# LiPower-Shield.net
KiCad netlist of a schematic drawn in EAGLE
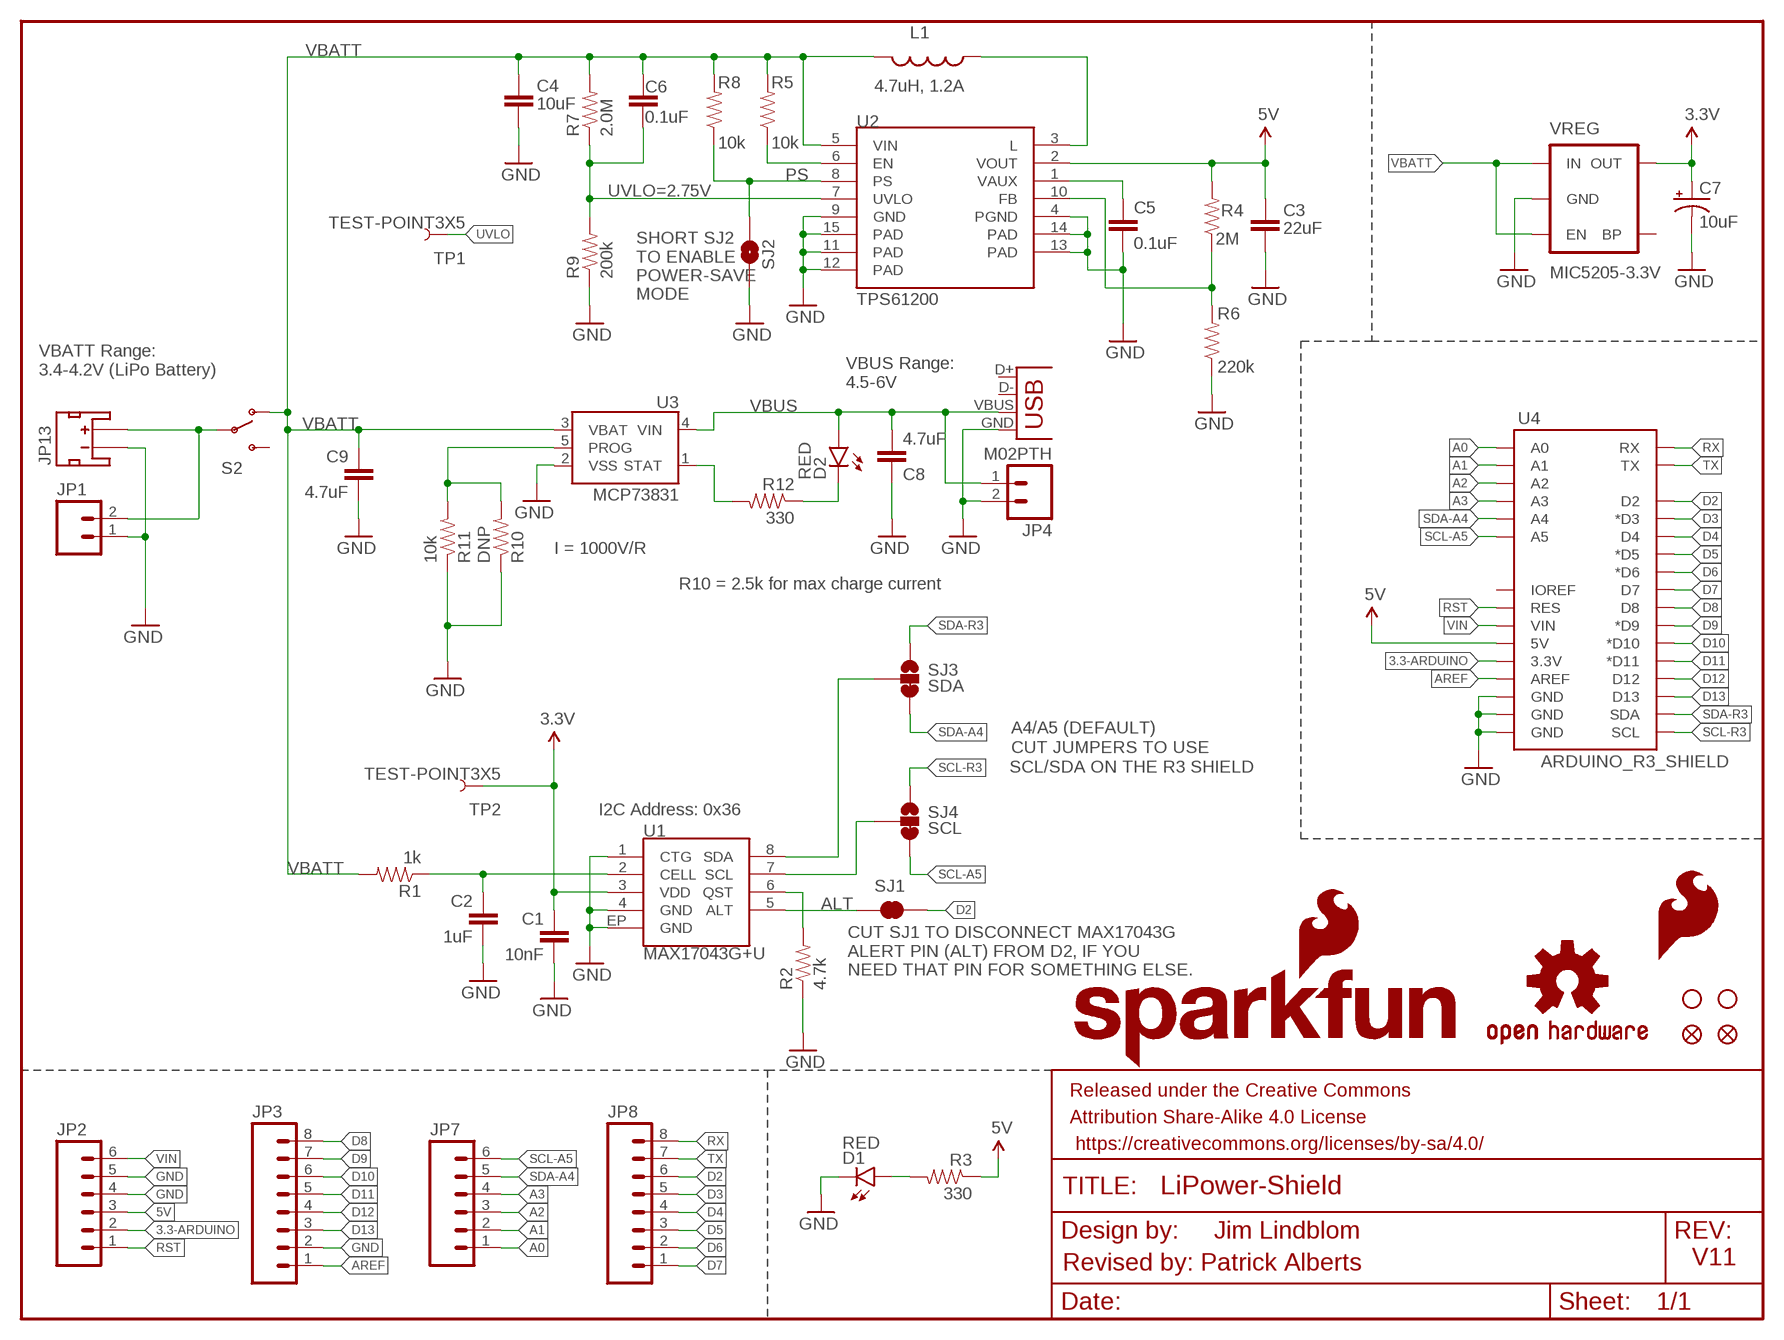
[diagram p0: schematic, sheet 1]

(export (version "E")
  (design (tool "Eeschema 10.0.6"))
  (components
    (comp (ref "C1")
      (value "10nF")
      (footprint "eagle-import:0603-CAP")
      (libsource (lib "eagle-import") (part "10NF/10000PF-50V-10%(0603)"))
    )
    (comp (ref "C2")
      (value "1uF")
      (footprint "eagle-import:0603-CAP")
      (libsource (lib "eagle-import") (part "1.0UF-16V-10%(0603)"))
    )
    (comp (ref "C3")
      (value "22uF")
      (footprint "eagle-import:0805")
      (libsource (lib "eagle-import") (part "22UF-6.3V-20%(0805)"))
    )
    (comp (ref "C4")
      (value "10uF")
      (footprint "eagle-import:1206")
      (libsource (lib "eagle-import") (part "10UF-6.3V-20%(1206)"))
    )
    (comp (ref "C5")
      (value "0.1uF")
      (footprint "eagle-import:0603-CAP")
      (libsource (lib "eagle-import") (part "0.1UF-25V(+80/-20%)(0603)"))
    )
    (comp (ref "C6")
      (value "0.1uF")
      (footprint "eagle-import:0603-CAP")
      (libsource (lib "eagle-import") (part "0.1UF-25V(+80/-20%)(0603)"))
    )
    (comp (ref "C7")
      (value "10uF")
      (footprint "eagle-import:EIA3216")
      (libsource (lib "eagle-import") (part "10UF-16V-10%(TANT)"))
    )
    (comp (ref "C8")
      (value "4.7uF")
      (footprint "eagle-import:0603-CAP")
      (libsource (lib "eagle-import") (part "4.7UF-6.3V-10%(0603)0603"))
    )
    (comp (ref "C9")
      (value "4.7uF")
      (footprint "eagle-import:0603-CAP")
      (libsource (lib "eagle-import") (part "4.7UF-6.3V-10%(0603)0603"))
    )
    (comp (ref "D1")
      (value "RED")
      (footprint "eagle-import:LED-0603")
      (libsource (lib "eagle-import") (part "LED-RED0603"))
    )
    (comp (ref "D2")
      (value "RED")
      (footprint "eagle-import:LED-0603")
      (libsource (lib "eagle-import") (part "LED-RED0603"))
    )
    (comp (ref "FID1")
      (value "FIDUCIAL1X2")
      (footprint "eagle-import:FIDUCIAL-1X2")
      (libsource (lib "eagle-import") (part "FIDUCIAL1X2"))
    )
    (comp (ref "FID2")
      (value "FIDUCIAL1X2")
      (footprint "eagle-import:FIDUCIAL-1X2")
      (libsource (lib "eagle-import") (part "FIDUCIAL1X2"))
    )
    (comp (ref "FRAME1")
      (value "FRAME-LETTER")
      (footprint "eagle-import:CREATIVE_COMMONS")
      (libsource (lib "eagle-import") (part "FRAME-LETTER"))
    )
    (comp (ref "JP1")
      (value "M021X02_NO_SILK")
      (footprint "eagle-import:1X02_NO_SILK")
      (libsource (lib "eagle-import") (part "M021X02_NO_SILK"))
    )
    (comp (ref "JP2")
      (value "M06NO_SILK")
      (footprint "eagle-import:1X06_NO_SILK")
      (libsource (lib "eagle-import") (part "M06NO_SILK"))
    )
    (comp (ref "JP3")
      (value "M08NO_SILK")
      (footprint "eagle-import:1X08_NO_SILK")
      (libsource (lib "eagle-import") (part "M08NO_SILK"))
    )
    (comp (ref "JP4")
      (value "M02PTH")
      (footprint "eagle-import:1X02")
      (libsource (lib "eagle-import") (part "SparkFun-Connectors_M02PTH"))
    )
    (comp (ref "JP7")
      (value "M06NO_SILK")
      (footprint "eagle-import:1X06_NO_SILK")
      (libsource (lib "eagle-import") (part "M06NO_SILK"))
    )
    (comp (ref "JP8")
      (value "M08NO_SILK")
      (footprint "eagle-import:1X08_NO_SILK")
      (libsource (lib "eagle-import") (part "M08NO_SILK"))
    )
    (comp (ref "JP9")
      (value "STAND-OFFTIGHT")
      (footprint "eagle-import:STAND-OFF-TIGHT")
      (libsource (lib "eagle-import") (part "STAND-OFFTIGHT"))
    )
    (comp (ref "JP10")
      (value "STAND-OFFTIGHT")
      (footprint "eagle-import:STAND-OFF-TIGHT")
      (libsource (lib "eagle-import") (part "STAND-OFFTIGHT"))
    )
    (comp (ref "JP11")
      (value "USBSMD")
      (footprint "eagle-import:USB-MINIB")
      (libsource (lib "eagle-import") (part "USBSMD"))
    )
    (comp (ref "JP13")
      (value "JST_2MM_MALE")
      (footprint "eagle-import:JST-2-SMD")
      (libsource (lib "eagle-import") (part "JST_2MM_MALE"))
    )
    (comp (ref "L1")
      (value "4.7uH, 1.2A")
      (footprint "eagle-import:INDUCTOR_4.7UH")
      (libsource (lib "eagle-import") (part "INDUCTORINDUCTOR_4.7UH"))
    )
    (comp (ref "LOGO1")
      (value "OSHW-LOGOS")
      (footprint "eagle-import:OSHW-LOGO-S")
      (libsource (lib "eagle-import") (part "OSHW-LOGOS"))
    )
    (comp (ref "LOGO2")
      (value "SFE_LOGO_NAME_FLAME.2_INCH")
      (footprint "eagle-import:SFE_LOGO_NAME_FLAME_.2")
      (libsource (lib "eagle-import") (part "SFE_LOGO_NAME_FLAME.2_INCH"))
    )
    (comp (ref "LOGO3")
      (value "SFE_LOGO_FLAME.1_INCH")
      (footprint "eagle-import:SFE_LOGO_FLAME_.1")
      (libsource (lib "eagle-import") (part "SFE_LOGO_FLAME.1_INCH"))
    )
    (comp (ref "R1")
      (value "1k")
      (footprint "eagle-import:0603-RES")
      (libsource (lib "eagle-import") (part "1KOHM1/10W1%(0603)"))
    )
    (comp (ref "R2")
      (value "4.7k")
      (footprint "eagle-import:0603-RES")
      (libsource (lib "eagle-import") (part "4.7KOHM1/10W1%(0603)"))
    )
    (comp (ref "R3")
      (value "330")
      (footprint "eagle-import:0603-RES")
      (libsource (lib "eagle-import") (part "330OHM1/10W1%(0603)"))
    )
    (comp (ref "R4")
      (value "2M")
      (footprint "eagle-import:0603-RES")
      (libsource (lib "eagle-import") (part "2MOHMS-1/10W-1%(0603)"))
    )
    (comp (ref "R5")
      (value "10k")
      (footprint "eagle-import:0603-RES")
      (libsource (lib "eagle-import") (part "10KOHM1/10W1%(0603)0603"))
    )
    (comp (ref "R6")
      (value "220k")
      (footprint "eagle-import:0603-RES")
      (libsource (lib "eagle-import") (part "220KOHM1/10W1%(0603)"))
    )
    (comp (ref "R7")
      (value "2.0M")
      (footprint "eagle-import:0603-RES")
      (libsource (lib "eagle-import") (part "2MOHMS-1/10W-1%(0603)"))
    )
    (comp (ref "R8")
      (value "10k")
      (footprint "eagle-import:0603-RES")
      (libsource (lib "eagle-import") (part "10KOHM1/10W1%(0603)0603"))
    )
    (comp (ref "R9")
      (value "200k")
      (footprint "eagle-import:0603-RES")
      (libsource (lib "eagle-import") (part "200KOHM1/10W1%(0603)200K"))
    )
    (comp (ref "R10")
      (value "DNP")
      (footprint "eagle-import:1_6W-RES")
      (libsource (lib "eagle-import") (part "RESISTORPTH-1/6W"))
    )
    (comp (ref "R11")
      (value "10k")
      (footprint "eagle-import:0603-RES")
      (libsource (lib "eagle-import") (part "10KOHM1/10W1%(0603)0603"))
    )
    (comp (ref "R12")
      (value "330")
      (footprint "eagle-import:0603-RES")
      (libsource (lib "eagle-import") (part "330OHM1/10W1%(0603)"))
    )
    (comp (ref "S2")
      (value "SWITCH-SPDT-SMD-A")
      (footprint "eagle-import:SWITCH-SPST-SMD-A")
      (libsource (lib "eagle-import") (part "SWITCH-SPDT-SMD-A"))
    )
    (comp (ref "SJ1")
      (value "SOLDERJUMPERTRACE")
      (footprint "eagle-import:SJ_2S-TRACE")
      (libsource (lib "eagle-import") (part "SOLDERJUMPERTRACE"))
    )
    (comp (ref "SJ2")
      (value "PS")
      (footprint "eagle-import:SJ_2S-NO")
      (libsource (lib "eagle-import") (part "SOLDERJUMPERNO"))
    )
    (comp (ref "SJ3")
      (value "SDA")
      (footprint "eagle-import:PAD-JUMPER-3-2OF3_NC_BY_TRACE_YES_SILK_FULL_BOX")
      (libsource (lib "eagle-import") (part "JUMPER-PAD-3-2OF3_NC_BY_TRACE"))
    )
    (comp (ref "SJ4")
      (value "SCL")
      (footprint "eagle-import:PAD-JUMPER-3-2OF3_NC_BY_TRACE_YES_SILK_FULL_BOX")
      (libsource (lib "eagle-import") (part "JUMPER-PAD-3-2OF3_NC_BY_TRACE"))
    )
    (comp (ref "TP1")
      (value "TEST-POINT3X5")
      (footprint "eagle-import:PAD.03X.05")
      (libsource (lib "eagle-import") (part "TEST-POINT3X5"))
    )
    (comp (ref "TP2")
      (value "TEST-POINT3X5")
      (footprint "eagle-import:PAD.03X.05")
      (libsource (lib "eagle-import") (part "TEST-POINT3X5"))
    )
    (comp (ref "U1")
      (value "MAX17043G+U")
      (footprint "eagle-import:TDFN-8")
      (libsource (lib "eagle-import") (part "MAX1704X"))
    )
    (comp (ref "U2")
      (value "TPS61200")
      (footprint "eagle-import:QFN-10_PAD")
      (libsource (lib "eagle-import") (part "TPS61200"))
    )
    (comp (ref "U3")
      (value "MCP73831")
      (footprint "eagle-import:SOT23-5")
      (libsource (lib "eagle-import") (part "MCP73831"))
    )
    (comp (ref "U4")
      (value "ARDUINO_R3_SHIELD")
      (footprint "eagle-import:UNO_R3_SHIELD")
      (libsource (lib "eagle-import") (part "ARDUINO_R3_SHIELD"))
    )
    (comp (ref "VREG")
      (value "MIC5205-3.3V")
      (footprint "eagle-import:SOT23-5")
      (libsource (lib "eagle-import") (part "MIC52053.3V"))
    )
  )
  (nets
    (net (code "1") (name "/ALT") (class "Default")
      (node (ref "SJ1") (pin "1") (pinfunction "1_1") (pintype "passive"))
      (node (ref "U1") (pin "5") (pinfunction "ALT_5") (pintype "bidirectional"))
    )
    (net (code "2") (name "/PS") (class "Default")
      (node (ref "R8") (pin "1") (pinfunction "1_1") (pintype "passive"))
      (node (ref "SJ2") (pin "2") (pinfunction "2_2") (pintype "passive"))
      (node (ref "U2") (pin "8") (pinfunction "PS_8") (pintype "input"))
    )
    (net (code "3") (name "/VBUS") (class "Default")
      (node (ref "C8") (pin "2") (pinfunction "2_2") (pintype "passive"))
      (node (ref "D2") (pin "A") (pinfunction "A_A") (pintype "passive"))
      (node (ref "JP11") (pin "VBUS") (pinfunction "VBUS_VBUS") (pintype "bidirectional"))
      (node (ref "JP4") (pin "1") (pinfunction "1_1") (pintype "passive"))
      (node (ref "U3") (pin "4") (pinfunction "VIN_4") (pintype "power_in"))
    )
    (net (code "4") (name "3.3-ARDUINO") (class "Default")
      (node (ref "JP2") (pin "2") (pinfunction "2_2") (pintype "passive"))
      (node (ref "U4") (pin "3.3V") (pinfunction "3.3V_3.3V") (pintype "bidirectional"))
    )
    (net (code "5") (name "3.3V") (class "Default")
      (node (ref "C1") (pin "1") (pinfunction "1_1") (pintype "passive"))
      (node (ref "C7") (pin "A") (pinfunction "+_A") (pintype "passive"))
      (node (ref "TP2") (pin "P$1") (pinfunction "1_P$1") (pintype "bidirectional"))
      (node (ref "U1") (pin "3") (pinfunction "VDD_3") (pintype "bidirectional"))
      (node (ref "VREG") (pin "5") (pinfunction "OUT_5") (pintype "passive"))
    )
    (net (code "6") (name "5V") (class "Default")
      (node (ref "C3") (pin "1") (pinfunction "1_1") (pintype "passive"))
      (node (ref "JP2") (pin "3") (pinfunction "3_3") (pintype "passive"))
      (node (ref "R3") (pin "1") (pinfunction "1_1") (pintype "passive"))
      (node (ref "R4") (pin "2") (pinfunction "2_2") (pintype "passive"))
      (node (ref "U2") (pin "2") (pinfunction "VOUT_2") (pintype "passive"))
      (node (ref "U4") (pin "5V") (pinfunction "5V_5V") (pintype "bidirectional"))
    )
    (net (code "7") (name "A0") (class "Default")
      (node (ref "JP7") (pin "1") (pinfunction "1_1") (pintype "passive"))
      (node (ref "U4") (pin "A0") (pinfunction "A0_A0") (pintype "bidirectional"))
    )
    (net (code "8") (name "A1") (class "Default")
      (node (ref "JP7") (pin "2") (pinfunction "2_2") (pintype "passive"))
      (node (ref "U4") (pin "A1") (pinfunction "A1_A1") (pintype "bidirectional"))
    )
    (net (code "9") (name "A2") (class "Default")
      (node (ref "JP7") (pin "3") (pinfunction "3_3") (pintype "passive"))
      (node (ref "U4") (pin "A2") (pinfunction "A2_A2") (pintype "bidirectional"))
    )
    (net (code "10") (name "A3") (class "Default")
      (node (ref "JP7") (pin "4") (pinfunction "4_4") (pintype "passive"))
      (node (ref "U4") (pin "A3") (pinfunction "A3_A3") (pintype "bidirectional"))
    )
    (net (code "11") (name "AREF") (class "Default")
      (node (ref "JP3") (pin "1") (pinfunction "1_1") (pintype "passive"))
      (node (ref "U4") (pin "AREF") (pinfunction "AREF_AREF") (pintype "bidirectional"))
    )
    (net (code "12") (name "D2") (class "Default")
      (node (ref "JP8") (pin "6") (pinfunction "6_6") (pintype "passive"))
      (node (ref "SJ1") (pin "2") (pinfunction "2_2") (pintype "passive"))
      (node (ref "U4") (pin "D2") (pinfunction "D2_D2") (pintype "bidirectional"))
    )
    (net (code "13") (name "D3") (class "Default")
      (node (ref "JP8") (pin "5") (pinfunction "5_5") (pintype "passive"))
      (node (ref "U4") (pin "D3") (pinfunction "*D3_D3") (pintype "bidirectional"))
    )
    (net (code "14") (name "D4") (class "Default")
      (node (ref "JP8") (pin "4") (pinfunction "4_4") (pintype "passive"))
      (node (ref "U4") (pin "D4") (pinfunction "D4_D4") (pintype "bidirectional"))
    )
    (net (code "15") (name "D5") (class "Default")
      (node (ref "JP8") (pin "3") (pinfunction "3_3") (pintype "passive"))
      (node (ref "U4") (pin "D5") (pinfunction "*D5_D5") (pintype "bidirectional"))
    )
    (net (code "16") (name "D6") (class "Default")
      (node (ref "JP8") (pin "2") (pinfunction "2_2") (pintype "passive"))
      (node (ref "U4") (pin "D6") (pinfunction "*D6_D6") (pintype "bidirectional"))
    )
    (net (code "17") (name "D7") (class "Default")
      (node (ref "JP8") (pin "1") (pinfunction "1_1") (pintype "passive"))
      (node (ref "U4") (pin "D7") (pinfunction "D7_D7") (pintype "bidirectional"))
    )
    (net (code "18") (name "D8") (class "Default")
      (node (ref "JP3") (pin "8") (pinfunction "8_8") (pintype "passive"))
      (node (ref "U4") (pin "D8") (pinfunction "D8_D8") (pintype "bidirectional"))
    )
    (net (code "19") (name "D9") (class "Default")
      (node (ref "JP3") (pin "7") (pinfunction "7_7") (pintype "passive"))
      (node (ref "U4") (pin "D9") (pinfunction "*D9_D9") (pintype "bidirectional"))
    )
    (net (code "20") (name "D10") (class "Default")
      (node (ref "JP3") (pin "6") (pinfunction "6_6") (pintype "passive"))
      (node (ref "U4") (pin "D10") (pinfunction "*D10_D10") (pintype "bidirectional"))
    )
    (net (code "21") (name "D11") (class "Default")
      (node (ref "JP3") (pin "5") (pinfunction "5_5") (pintype "passive"))
      (node (ref "U4") (pin "D11") (pinfunction "*D11_D11") (pintype "bidirectional"))
    )
    (net (code "22") (name "D12") (class "Default")
      (node (ref "JP3") (pin "4") (pinfunction "4_4") (pintype "passive"))
      (node (ref "U4") (pin "D12") (pinfunction "D12_D12") (pintype "bidirectional"))
    )
    (net (code "23") (name "D13") (class "Default")
      (node (ref "JP3") (pin "3") (pinfunction "3_3") (pintype "passive"))
      (node (ref "U4") (pin "D13") (pinfunction "D13_D13") (pintype "bidirectional"))
    )
    (net (code "24") (name "GND") (class "Default")
      (node (ref "C1") (pin "2") (pinfunction "2_2") (pintype "passive"))
      (node (ref "C2") (pin "2") (pinfunction "2_2") (pintype "passive"))
      (node (ref "C3") (pin "2") (pinfunction "2_2") (pintype "passive"))
      (node (ref "C4") (pin "2") (pinfunction "2_2") (pintype "passive"))
      (node (ref "C5") (pin "2") (pinfunction "2_2") (pintype "passive"))
      (node (ref "C7") (pin "C") (pinfunction "-_C") (pintype "passive"))
      (node (ref "C8") (pin "1") (pinfunction "1_1") (pintype "passive"))
      (node (ref "C9") (pin "2") (pinfunction "2_2") (pintype "passive"))
      (node (ref "D1") (pin "C") (pinfunction "C_C") (pintype "passive"))
      (node (ref "JP1") (pin "1") (pinfunction "1_1") (pintype "passive"))
      (node (ref "JP11") (pin "GND") (pinfunction "GND_GND") (pintype "bidirectional"))
      (node (ref "JP13") (pin "1") (pinfunction "-_1") (pintype "bidirectional"))
      (node (ref "JP2") (pin "4") (pinfunction "4_4") (pintype "passive"))
      (node (ref "JP2") (pin "5") (pinfunction "5_5") (pintype "passive"))
      (node (ref "JP3") (pin "2") (pinfunction "2_2") (pintype "passive"))
      (node (ref "JP4") (pin "2") (pinfunction "2_2") (pintype "passive"))
      (node (ref "R10") (pin "1") (pinfunction "1_1") (pintype "passive"))
      (node (ref "R11") (pin "1") (pinfunction "1_1") (pintype "passive"))
      (node (ref "R2") (pin "1") (pinfunction "1_1") (pintype "passive"))
      (node (ref "R6") (pin "1") (pinfunction "1_1") (pintype "passive"))
      (node (ref "R9") (pin "1") (pinfunction "1_1") (pintype "passive"))
      (node (ref "SJ2") (pin "1") (pinfunction "1_1") (pintype "passive"))
      (node (ref "U1") (pin "1") (pinfunction "CTG_1") (pintype "bidirectional"))
      (node (ref "U1") (pin "4") (pinfunction "GND_4") (pintype "bidirectional"))
      (node (ref "U1") (pin "EP") (pinfunction "GND_EP") (pintype "bidirectional"))
      (node (ref "U2") (pin "11") (pinfunction "PAD_11") (pintype "power_in"))
      (node (ref "U2") (pin "12") (pinfunction "PAD_12") (pintype "power_in"))
      (node (ref "U2") (pin "13") (pinfunction "PAD_13") (pintype "power_in"))
      (node (ref "U2") (pin "14") (pinfunction "PAD_14") (pintype "power_in"))
      (node (ref "U2") (pin "15") (pinfunction "PAD_15") (pintype "power_in"))
      (node (ref "U2") (pin "4") (pinfunction "PGND_4") (pintype "power_in"))
      (node (ref "U2") (pin "9") (pinfunction "GND_9") (pintype "power_in"))
      (node (ref "U3") (pin "2") (pinfunction "VSS_2") (pintype "power_in"))
      (node (ref "U4") (pin "GND@0") (pinfunction "GND_GND@0") (pintype "bidirectional"))
      (node (ref "U4") (pin "GND@1") (pinfunction "GND_GND@1") (pintype "bidirectional"))
      (node (ref "U4") (pin "GND@2") (pinfunction "GND_GND@2") (pintype "bidirectional"))
      (node (ref "VREG") (pin "2") (pinfunction "GND_2") (pintype "input"))
    )
    (net (code "25") (name "Net-(D1-PadA)") (class "Default")
      (node (ref "D1") (pin "A") (pinfunction "A_A") (pintype "passive"))
      (node (ref "R3") (pin "2") (pinfunction "2_2") (pintype "passive"))
    )
    (net (code "26") (name "Net-(D2-PadC)") (class "Default")
      (node (ref "D2") (pin "C") (pinfunction "C_C") (pintype "passive"))
      (node (ref "R12") (pin "1") (pinfunction "1_1") (pintype "passive"))
    )
    (net (code "27") (name "Net-(JP13-+)") (class "Default")
      (node (ref "JP1") (pin "2") (pinfunction "2_2") (pintype "passive"))
      (node (ref "JP13") (pin "2") (pinfunction "+_2") (pintype "bidirectional"))
      (node (ref "S2") (pin "2") (pinfunction "P_2") (pintype "passive"))
    )
    (net (code "28") (name "Net-(L1-1)") (class "Default")
      (node (ref "L1") (pin "P$1") (pinfunction "1_P$1") (pintype "passive"))
      (node (ref "U2") (pin "3") (pinfunction "L_3") (pintype "passive"))
    )
    (net (code "29") (name "Net-(U1-CELL)") (class "Default")
      (node (ref "C2") (pin "1") (pinfunction "1_1") (pintype "passive"))
      (node (ref "R1") (pin "1") (pinfunction "1_1") (pintype "passive"))
      (node (ref "U1") (pin "2") (pinfunction "CELL_2") (pintype "bidirectional"))
    )
    (net (code "30") (name "Net-(U1-QST)") (class "Default")
      (node (ref "R2") (pin "2") (pinfunction "2_2") (pintype "passive"))
      (node (ref "U1") (pin "6") (pinfunction "QST_6") (pintype "bidirectional"))
    )
    (net (code "31") (name "Net-(U1-SCL)") (class "Default")
      (node (ref "SJ4") (pin "2") (pinfunction "2_2") (pintype "passive"))
      (node (ref "U1") (pin "7") (pinfunction "SCL_7") (pintype "bidirectional"))
    )
    (net (code "32") (name "Net-(U1-SDA)") (class "Default")
      (node (ref "SJ3") (pin "2") (pinfunction "2_2") (pintype "passive"))
      (node (ref "U1") (pin "8") (pinfunction "SDA_8") (pintype "bidirectional"))
    )
    (net (code "33") (name "Net-(U2-EN)") (class "Default")
      (node (ref "R5") (pin "1") (pinfunction "1_1") (pintype "passive"))
      (node (ref "U2") (pin "6") (pinfunction "EN_6") (pintype "input"))
    )
    (net (code "34") (name "Net-(U2-FB)") (class "Default")
      (node (ref "R4") (pin "1") (pinfunction "1_1") (pintype "passive"))
      (node (ref "R6") (pin "2") (pinfunction "2_2") (pintype "passive"))
      (node (ref "U2") (pin "10") (pinfunction "FB_10") (pintype "passive"))
    )
    (net (code "35") (name "Net-(U2-VAUX)") (class "Default")
      (node (ref "C5") (pin "1") (pinfunction "1_1") (pintype "passive"))
      (node (ref "U2") (pin "1") (pinfunction "VAUX_1") (pintype "passive"))
    )
    (net (code "36") (name "Net-(U3-PROG)") (class "Default")
      (node (ref "R10") (pin "2") (pinfunction "2_2") (pintype "passive"))
      (node (ref "R11") (pin "2") (pinfunction "2_2") (pintype "passive"))
      (node (ref "U3") (pin "5") (pinfunction "PROG_5") (pintype "input"))
    )
    (net (code "37") (name "Net-(U3-STAT)") (class "Default")
      (node (ref "R12") (pin "2") (pinfunction "2_2") (pintype "passive"))
      (node (ref "U3") (pin "1") (pinfunction "STAT_1") (pintype "output"))
    )
    (net (code "38") (name "RST") (class "Default")
      (node (ref "JP2") (pin "1") (pinfunction "1_1") (pintype "passive"))
      (node (ref "U4") (pin "RES") (pinfunction "RES_RES") (pintype "bidirectional"))
    )
    (net (code "39") (name "RX") (class "Default")
      (node (ref "JP8") (pin "8") (pinfunction "8_8") (pintype "passive"))
      (node (ref "U4") (pin "RX") (pinfunction "RX_RX") (pintype "bidirectional"))
    )
    (net (code "40") (name "SCL-A5") (class "Default")
      (node (ref "JP7") (pin "6") (pinfunction "6_6") (pintype "passive"))
      (node (ref "SJ4") (pin "3") (pinfunction "3_3") (pintype "passive"))
      (node (ref "U4") (pin "A5") (pinfunction "A5_A5") (pintype "bidirectional"))
    )
    (net (code "41") (name "SCL-R3") (class "Default")
      (node (ref "SJ4") (pin "1") (pinfunction "1_1") (pintype "passive"))
      (node (ref "U4") (pin "SCL") (pinfunction "SCL_SCL") (pintype "bidirectional"))
    )
    (net (code "42") (name "SDA-A4") (class "Default")
      (node (ref "JP7") (pin "5") (pinfunction "5_5") (pintype "passive"))
      (node (ref "SJ3") (pin "3") (pinfunction "3_3") (pintype "passive"))
      (node (ref "U4") (pin "A4") (pinfunction "A4_A4") (pintype "bidirectional"))
    )
    (net (code "43") (name "SDA-R3") (class "Default")
      (node (ref "SJ3") (pin "1") (pinfunction "1_1") (pintype "passive"))
      (node (ref "U4") (pin "SDA") (pinfunction "SDA_SDA") (pintype "bidirectional"))
    )
    (net (code "44") (name "TX") (class "Default")
      (node (ref "JP8") (pin "7") (pinfunction "7_7") (pintype "passive"))
      (node (ref "U4") (pin "TX") (pinfunction "TX_TX") (pintype "bidirectional"))
    )
    (net (code "45") (name "UVLO") (class "Default")
      (node (ref "C6") (pin "2") (pinfunction "2_2") (pintype "passive"))
      (node (ref "R7") (pin "1") (pinfunction "1_1") (pintype "passive"))
      (node (ref "R9") (pin "2") (pinfunction "2_2") (pintype "passive"))
      (node (ref "TP1") (pin "P$1") (pinfunction "1_P$1") (pintype "bidirectional"))
      (node (ref "U2") (pin "7") (pinfunction "UVLO_7") (pintype "passive"))
    )
    (net (code "46") (name "VBATT") (class "Default")
      (node (ref "C4") (pin "1") (pinfunction "1_1") (pintype "passive"))
      (node (ref "C6") (pin "1") (pinfunction "1_1") (pintype "passive"))
      (node (ref "C9") (pin "1") (pinfunction "1_1") (pintype "passive"))
      (node (ref "L1") (pin "P$2") (pinfunction "2_P$2") (pintype "passive"))
      (node (ref "R1") (pin "2") (pinfunction "2_2") (pintype "passive"))
      (node (ref "R5") (pin "2") (pinfunction "2_2") (pintype "passive"))
      (node (ref "R7") (pin "2") (pinfunction "2_2") (pintype "passive"))
      (node (ref "R8") (pin "2") (pinfunction "2_2") (pintype "passive"))
      (node (ref "S2") (pin "1") (pinfunction "O_1") (pintype "passive"))
      (node (ref "U2") (pin "5") (pinfunction "VIN_5") (pintype "power_in"))
      (node (ref "U3") (pin "3") (pinfunction "VBAT_3") (pintype "power_in"))
      (node (ref "VREG") (pin "1") (pinfunction "IN_1") (pintype "input"))
      (node (ref "VREG") (pin "3") (pinfunction "EN_3") (pintype "input"))
    )
    (net (code "47") (name "VIN") (class "Default")
      (node (ref "JP2") (pin "6") (pinfunction "6_6") (pintype "passive"))
      (node (ref "U4") (pin "VIN") (pinfunction "VIN_VIN") (pintype "bidirectional"))
    )
    (net (code "48") (name "unconnected-(JP11-PadD+)") (class "Default")
      (node (ref "JP11") (pin "D+") (pinfunction "D+_D+") (pintype "bidirectional"))
    )
    (net (code "49") (name "unconnected-(JP11-PadD-)") (class "Default")
      (node (ref "JP11") (pin "D-") (pinfunction "D-_D-") (pintype "bidirectional"))
    )
    (net (code "50") (name "unconnected-(JP13-PAD1-PadNC1)") (class "Default")
      (node (ref "JP13") (pin "NC1") (pinfunction "PAD1_NC1") (pintype "bidirectional"))
    )
    (net (code "51") (name "unconnected-(JP13-PAD2-PadNC2)") (class "Default")
      (node (ref "JP13") (pin "NC2") (pinfunction "PAD2_NC2") (pintype "bidirectional"))
    )
    (net (code "52") (name "unconnected-(S2-S-Pad3)") (class "Default")
      (node (ref "S2") (pin "3") (pinfunction "S_3") (pintype "passive"))
    )
    (net (code "53") (name "unconnected-(U4-PadIOREF)") (class "Default")
      (node (ref "U4") (pin "IOREF") (pinfunction "IOREF_IOREF") (pintype "bidirectional"))
    )
    (net (code "54") (name "unconnected-(VREG-BP-Pad4)") (class "Default")
      (node (ref "VREG") (pin "4") (pinfunction "BP_4") (pintype "input"))
    )
  )
)
